# PCB-BI8-1x8.net
KiCad netlist of a schematic drawn in EAGLE
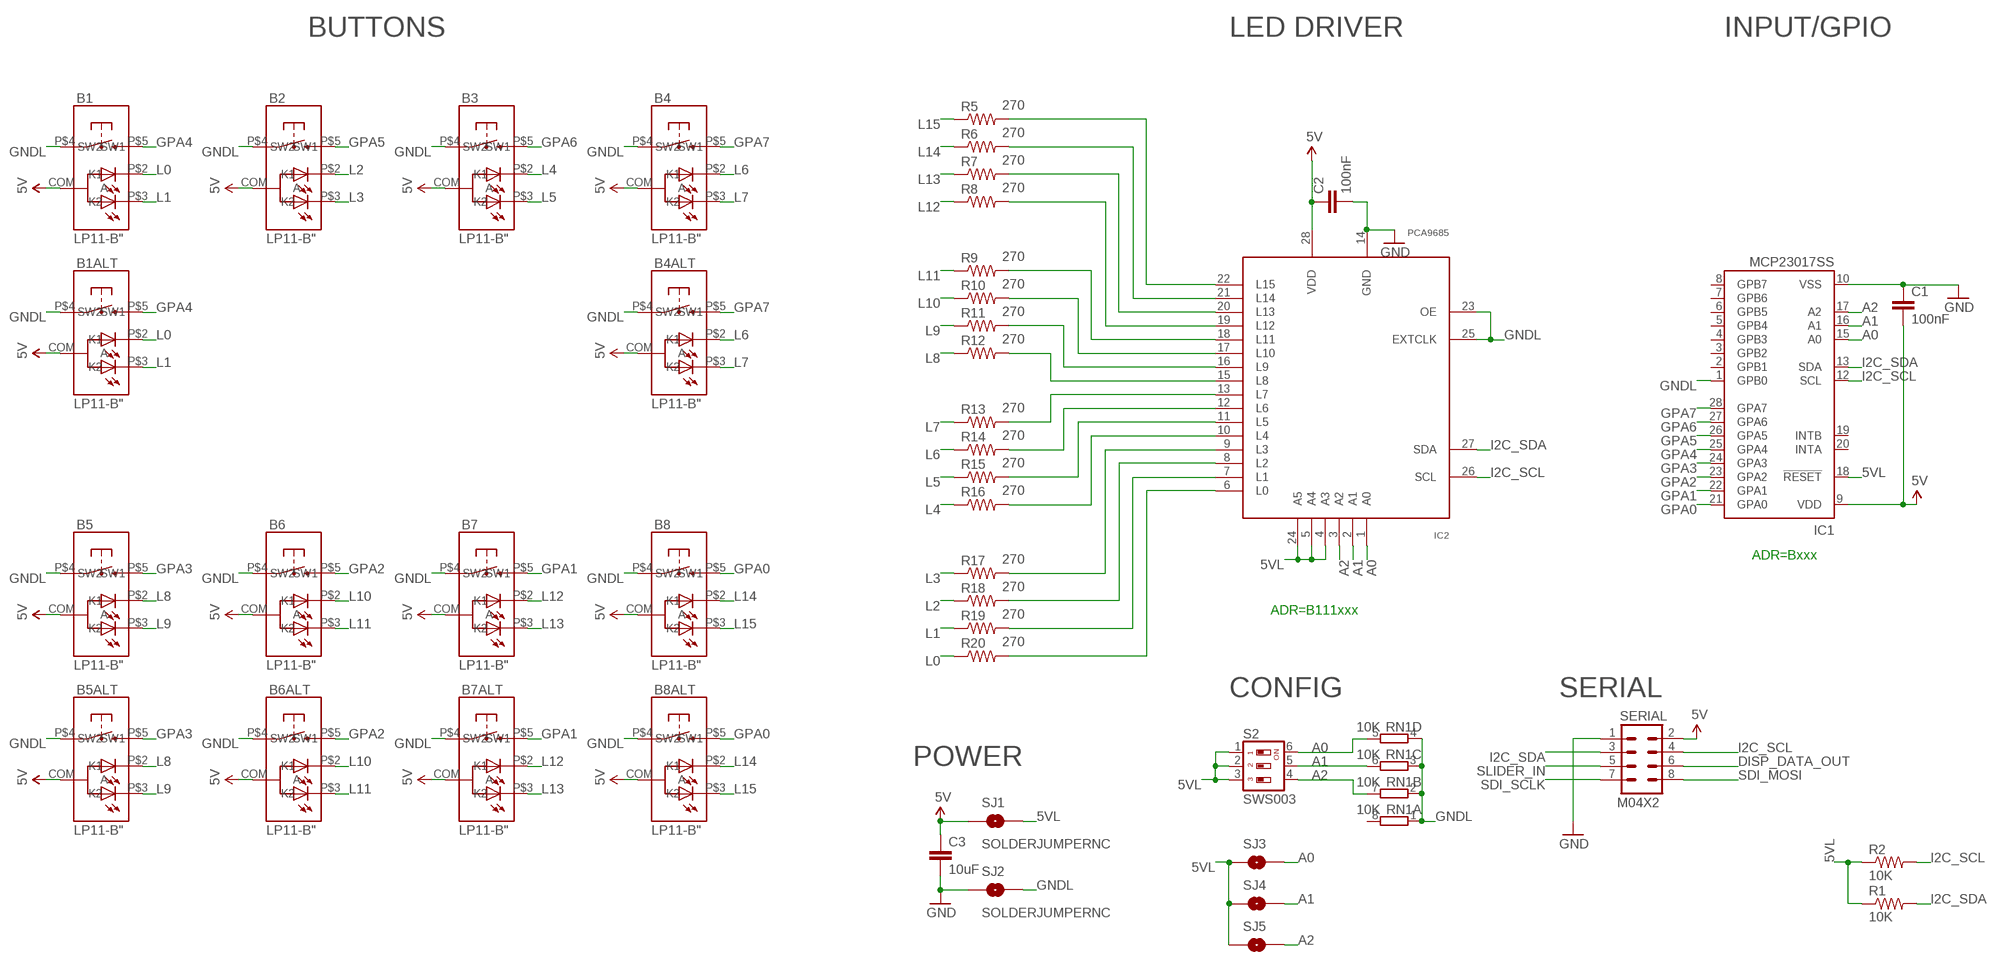
[diagram p0: schematic, sheet 1]

(export (version "E")
  (design (tool "Eeschema 10.0.6"))
  (components
    (comp (ref "B1")
      (value "LP11-B\"")
      (footprint "eagle-import:LP11")
      (libsource (lib "eagle-import") (part "LP11-B{dblquote}"))
    )
    (comp (ref "B1ALT")
      (value "LP11-B\"")
      (footprint "eagle-import:LP11")
      (libsource (lib "eagle-import") (part "LP11-B{dblquote}"))
    )
    (comp (ref "B2")
      (value "LP11-B\"")
      (footprint "eagle-import:LP11")
      (libsource (lib "eagle-import") (part "LP11-B{dblquote}"))
    )
    (comp (ref "B3")
      (value "LP11-B\"")
      (footprint "eagle-import:LP11")
      (libsource (lib "eagle-import") (part "LP11-B{dblquote}"))
    )
    (comp (ref "B4")
      (value "LP11-B\"")
      (footprint "eagle-import:LP11")
      (libsource (lib "eagle-import") (part "LP11-B{dblquote}"))
    )
    (comp (ref "B4ALT")
      (value "LP11-B\"")
      (footprint "eagle-import:LP11")
      (libsource (lib "eagle-import") (part "LP11-B{dblquote}"))
    )
    (comp (ref "B5")
      (value "LP11-B\"")
      (footprint "eagle-import:LP11")
      (libsource (lib "eagle-import") (part "LP11-B{dblquote}"))
    )
    (comp (ref "B5ALT")
      (value "LP11-B\"")
      (footprint "eagle-import:LP11")
      (libsource (lib "eagle-import") (part "LP11-B{dblquote}"))
    )
    (comp (ref "B6")
      (value "LP11-B\"")
      (footprint "eagle-import:LP11")
      (libsource (lib "eagle-import") (part "LP11-B{dblquote}"))
    )
    (comp (ref "B6ALT")
      (value "LP11-B\"")
      (footprint "eagle-import:LP11")
      (libsource (lib "eagle-import") (part "LP11-B{dblquote}"))
    )
    (comp (ref "B7")
      (value "LP11-B\"")
      (footprint "eagle-import:LP11")
      (libsource (lib "eagle-import") (part "LP11-B{dblquote}"))
    )
    (comp (ref "B7ALT")
      (value "LP11-B\"")
      (footprint "eagle-import:LP11")
      (libsource (lib "eagle-import") (part "LP11-B{dblquote}"))
    )
    (comp (ref "B8")
      (value "LP11-B\"")
      (footprint "eagle-import:LP11")
      (libsource (lib "eagle-import") (part "LP11-B{dblquote}"))
    )
    (comp (ref "B8ALT")
      (value "LP11-B\"")
      (footprint "eagle-import:LP11")
      (libsource (lib "eagle-import") (part "LP11-B{dblquote}"))
    )
    (comp (ref "C1")
      (value "100nF")
      (footprint "eagle-import:0603-CAP")
      (libsource (lib "eagle-import") (part "CAP0603-CAP"))
    )
    (comp (ref "C2")
      (value "100nF")
      (footprint "eagle-import:0603-CAP")
      (libsource (lib "eagle-import") (part "CAP0603-CAP"))
    )
    (comp (ref "C3")
      (value "10uF")
      (footprint "eagle-import:0805")
      (libsource (lib "eagle-import") (part "CAP0805"))
    )
    (comp (ref "IC1")
      (value "MCP23017SS")
      (footprint "eagle-import:SSOP28")
      (fields
        (field (name "MF") "MICROCHIP")
        (field (name "MPN") "MCP23017-E/SS")
        (field (name "MPN_1") "MCP23017-E/SS")
        (field (name "OC_FARNELL") "1467674")
        (field (name "OC_NEWARK") "31K2960")
      )
      (libsource (lib "eagle-import") (part "MCP23017SS"))
    )
    (comp (ref "IC2")
      (value "PCA9685")
      (footprint "eagle-import:TSSOP28")
      (libsource (lib "eagle-import") (part "PCA9685"))
    )
    (comp (ref "R1")
      (value "10K")
      (footprint "eagle-import:0603-RES")
      (libsource (lib "eagle-import") (part "RESISTOR0603-RES"))
    )
    (comp (ref "R2")
      (value "10K")
      (footprint "eagle-import:0603-RES")
      (libsource (lib "eagle-import") (part "RESISTOR0603-RES"))
    )
    (comp (ref "R5")
      (value "270")
      (footprint "eagle-import:0603-RES")
      (libsource (lib "eagle-import") (part "RESISTOR0603-RES"))
    )
    (comp (ref "R6")
      (value "270")
      (footprint "eagle-import:0603-RES")
      (libsource (lib "eagle-import") (part "RESISTOR0603-RES"))
    )
    (comp (ref "R7")
      (value "270")
      (footprint "eagle-import:0603-RES")
      (libsource (lib "eagle-import") (part "RESISTOR0603-RES"))
    )
    (comp (ref "R8")
      (value "270")
      (footprint "eagle-import:0603-RES")
      (libsource (lib "eagle-import") (part "RESISTOR0603-RES"))
    )
    (comp (ref "R9")
      (value "270")
      (footprint "eagle-import:0603-RES")
      (libsource (lib "eagle-import") (part "RESISTOR0603-RES"))
    )
    (comp (ref "R10")
      (value "270")
      (footprint "eagle-import:0603-RES")
      (libsource (lib "eagle-import") (part "RESISTOR0603-RES"))
    )
    (comp (ref "R11")
      (value "270")
      (footprint "eagle-import:0603-RES")
      (libsource (lib "eagle-import") (part "RESISTOR0603-RES"))
    )
    (comp (ref "R12")
      (value "270")
      (footprint "eagle-import:0603-RES")
      (libsource (lib "eagle-import") (part "RESISTOR0603-RES"))
    )
    (comp (ref "R13")
      (value "270")
      (footprint "eagle-import:0603-RES")
      (libsource (lib "eagle-import") (part "RESISTOR0603-RES"))
    )
    (comp (ref "R14")
      (value "270")
      (footprint "eagle-import:0603-RES")
      (libsource (lib "eagle-import") (part "RESISTOR0603-RES"))
    )
    (comp (ref "R15")
      (value "270")
      (footprint "eagle-import:0603-RES")
      (libsource (lib "eagle-import") (part "RESISTOR0603-RES"))
    )
    (comp (ref "R16")
      (value "270")
      (footprint "eagle-import:0603-RES")
      (libsource (lib "eagle-import") (part "RESISTOR0603-RES"))
    )
    (comp (ref "R17")
      (value "270")
      (footprint "eagle-import:0603-RES")
      (libsource (lib "eagle-import") (part "RESISTOR0603-RES"))
    )
    (comp (ref "R18")
      (value "270")
      (footprint "eagle-import:0603-RES")
      (libsource (lib "eagle-import") (part "RESISTOR0603-RES"))
    )
    (comp (ref "R19")
      (value "270")
      (footprint "eagle-import:0603-RES")
      (libsource (lib "eagle-import") (part "RESISTOR0603-RES"))
    )
    (comp (ref "R20")
      (value "270")
      (footprint "eagle-import:0603-RES")
      (libsource (lib "eagle-import") (part "RESISTOR0603-RES"))
    )
    (comp (ref "RN1")
      (value "10K")
      (footprint "eagle-import:CAY16_HAND")
      (libsource (lib "eagle-import") (part "4R-NCAY16"))
    )
    (comp (ref "S2")
      (value "SWS003")
      (footprint "eagle-import:SMS-003")
      (libsource (lib "eagle-import") (part "SWS003"))
    )
    (comp (ref "SERIAL")
      (value "M04X2")
      (footprint "eagle-import:2X4")
      (libsource (lib "eagle-import") (part "M04X2"))
    )
    (comp (ref "SJ1")
      (value "SOLDERJUMPERNC")
      (footprint "eagle-import:SJ_2S")
      (libsource (lib "eagle-import") (part "SOLDERJUMPERNC"))
    )
    (comp (ref "SJ2")
      (value "SOLDERJUMPERNC")
      (footprint "eagle-import:SJ_2S")
      (libsource (lib "eagle-import") (part "SOLDERJUMPERNC"))
    )
    (comp (ref "SJ3")
      (value "SOLDERJUMPERNC")
      (footprint "eagle-import:SJ_2S")
      (libsource (lib "eagle-import") (part "SOLDERJUMPERNC"))
    )
    (comp (ref "SJ4")
      (value "SOLDERJUMPERNC")
      (footprint "eagle-import:SJ_2S")
      (libsource (lib "eagle-import") (part "SOLDERJUMPERNC"))
    )
    (comp (ref "SJ5")
      (value "SOLDERJUMPERNC")
      (footprint "eagle-import:SJ_2S")
      (libsource (lib "eagle-import") (part "SOLDERJUMPERNC"))
    )
  )
  (nets
    (net (code "1") (name "/5VL") (class "Default")
      (node (ref "IC1") (pin "18") (pinfunction "~{RESET}_18") (pintype "input"))
      (node (ref "IC2") (pin "24") (pinfunction "A5_24") (pintype "input"))
      (node (ref "IC2") (pin "4") (pinfunction "A3_4") (pintype "input"))
      (node (ref "IC2") (pin "5") (pinfunction "A4_5") (pintype "input"))
      (node (ref "R1") (pin "1") (pinfunction "1_1") (pintype "passive"))
      (node (ref "R2") (pin "1") (pinfunction "1_1") (pintype "passive"))
      (node (ref "S2") (pin "1") (pinfunction "1_1") (pintype "passive"))
      (node (ref "S2") (pin "2") (pinfunction "2_2") (pintype "passive"))
      (node (ref "S2") (pin "3") (pinfunction "3_3") (pintype "passive"))
      (node (ref "SJ1") (pin "2") (pinfunction "2_2") (pintype "passive"))
      (node (ref "SJ3") (pin "1") (pinfunction "1_1") (pintype "passive"))
      (node (ref "SJ4") (pin "1") (pinfunction "1_1") (pintype "passive"))
      (node (ref "SJ5") (pin "1") (pinfunction "1_1") (pintype "passive"))
    )
    (net (code "2") (name "/A0") (class "Default")
      (node (ref "IC1") (pin "15") (pinfunction "A0_15") (pintype "input"))
      (node (ref "IC2") (pin "1") (pinfunction "A0_1") (pintype "input"))
      (node (ref "RN1") (pin "5") (pinfunction "2_5") (pintype "passive"))
      (node (ref "S2") (pin "6") (pinfunction "6_6") (pintype "passive"))
      (node (ref "SJ3") (pin "2") (pinfunction "2_2") (pintype "passive"))
    )
    (net (code "3") (name "/A1") (class "Default")
      (node (ref "IC1") (pin "16") (pinfunction "A1_16") (pintype "input"))
      (node (ref "IC2") (pin "2") (pinfunction "A1_2") (pintype "input"))
      (node (ref "RN1") (pin "6") (pinfunction "2_6") (pintype "passive"))
      (node (ref "S2") (pin "5") (pinfunction "5_5") (pintype "passive"))
      (node (ref "SJ4") (pin "2") (pinfunction "2_2") (pintype "passive"))
    )
    (net (code "4") (name "/A2") (class "Default")
      (node (ref "IC1") (pin "17") (pinfunction "A2_17") (pintype "input"))
      (node (ref "IC2") (pin "3") (pinfunction "A2_3") (pintype "input"))
      (node (ref "RN1") (pin "7") (pinfunction "2_7") (pintype "passive"))
      (node (ref "S2") (pin "4") (pinfunction "4_4") (pintype "passive"))
      (node (ref "SJ5") (pin "2") (pinfunction "2_2") (pintype "passive"))
    )
    (net (code "5") (name "/DISP_DATA_OUT") (class "Default")
      (node (ref "SERIAL") (pin "6") (pinfunction "6_6") (pintype "passive"))
    )
    (net (code "6") (name "/GNDL") (class "Default")
      (node (ref "B1") (pin "P$4") (pinfunction "SW1_P$4") (pintype "bidirectional"))
      (node (ref "B1ALT") (pin "P$4") (pinfunction "SW1_P$4") (pintype "bidirectional"))
      (node (ref "B2") (pin "P$4") (pinfunction "SW1_P$4") (pintype "bidirectional"))
      (node (ref "B3") (pin "P$4") (pinfunction "SW1_P$4") (pintype "bidirectional"))
      (node (ref "B4") (pin "P$4") (pinfunction "SW1_P$4") (pintype "bidirectional"))
      (node (ref "B4ALT") (pin "P$4") (pinfunction "SW1_P$4") (pintype "bidirectional"))
      (node (ref "B5") (pin "P$4") (pinfunction "SW1_P$4") (pintype "bidirectional"))
      (node (ref "B5ALT") (pin "P$4") (pinfunction "SW1_P$4") (pintype "bidirectional"))
      (node (ref "B6") (pin "P$4") (pinfunction "SW1_P$4") (pintype "bidirectional"))
      (node (ref "B6ALT") (pin "P$4") (pinfunction "SW1_P$4") (pintype "bidirectional"))
      (node (ref "B7") (pin "P$4") (pinfunction "SW1_P$4") (pintype "bidirectional"))
      (node (ref "B7ALT") (pin "P$4") (pinfunction "SW1_P$4") (pintype "bidirectional"))
      (node (ref "B8") (pin "P$4") (pinfunction "SW1_P$4") (pintype "bidirectional"))
      (node (ref "B8ALT") (pin "P$4") (pinfunction "SW1_P$4") (pintype "bidirectional"))
      (node (ref "IC1") (pin "1") (pinfunction "GPB0_1") (pintype "bidirectional"))
      (node (ref "IC2") (pin "23") (pinfunction "OE_23") (pintype "input"))
      (node (ref "IC2") (pin "25") (pinfunction "EXTCLK_25") (pintype "input"))
      (node (ref "RN1") (pin "1") (pinfunction "1_1") (pintype "passive"))
      (node (ref "RN1") (pin "2") (pinfunction "1_2") (pintype "passive"))
      (node (ref "RN1") (pin "3") (pinfunction "1_3") (pintype "passive"))
      (node (ref "RN1") (pin "4") (pinfunction "1_4") (pintype "passive"))
      (node (ref "SJ2") (pin "2") (pinfunction "2_2") (pintype "passive"))
    )
    (net (code "7") (name "/GPA0") (class "Default")
      (node (ref "B8") (pin "P$5") (pinfunction "SW2_P$5") (pintype "bidirectional"))
      (node (ref "B8ALT") (pin "P$5") (pinfunction "SW2_P$5") (pintype "bidirectional"))
      (node (ref "IC1") (pin "21") (pinfunction "GPA0_21") (pintype "bidirectional"))
    )
    (net (code "8") (name "/GPA1") (class "Default")
      (node (ref "B7") (pin "P$5") (pinfunction "SW2_P$5") (pintype "bidirectional"))
      (node (ref "B7ALT") (pin "P$5") (pinfunction "SW2_P$5") (pintype "bidirectional"))
      (node (ref "IC1") (pin "22") (pinfunction "GPA1_22") (pintype "bidirectional"))
    )
    (net (code "9") (name "/GPA2") (class "Default")
      (node (ref "B6") (pin "P$5") (pinfunction "SW2_P$5") (pintype "bidirectional"))
      (node (ref "B6ALT") (pin "P$5") (pinfunction "SW2_P$5") (pintype "bidirectional"))
      (node (ref "IC1") (pin "23") (pinfunction "GPA2_23") (pintype "bidirectional"))
    )
    (net (code "10") (name "/GPA3") (class "Default")
      (node (ref "B5") (pin "P$5") (pinfunction "SW2_P$5") (pintype "bidirectional"))
      (node (ref "B5ALT") (pin "P$5") (pinfunction "SW2_P$5") (pintype "bidirectional"))
      (node (ref "IC1") (pin "24") (pinfunction "GPA3_24") (pintype "bidirectional"))
    )
    (net (code "11") (name "/GPA4") (class "Default")
      (node (ref "B1") (pin "P$5") (pinfunction "SW2_P$5") (pintype "bidirectional"))
      (node (ref "B1ALT") (pin "P$5") (pinfunction "SW2_P$5") (pintype "bidirectional"))
      (node (ref "IC1") (pin "25") (pinfunction "GPA4_25") (pintype "bidirectional"))
    )
    (net (code "12") (name "/GPA5") (class "Default")
      (node (ref "B2") (pin "P$5") (pinfunction "SW2_P$5") (pintype "bidirectional"))
      (node (ref "IC1") (pin "26") (pinfunction "GPA5_26") (pintype "bidirectional"))
    )
    (net (code "13") (name "/GPA6") (class "Default")
      (node (ref "B3") (pin "P$5") (pinfunction "SW2_P$5") (pintype "bidirectional"))
      (node (ref "IC1") (pin "27") (pinfunction "GPA6_27") (pintype "bidirectional"))
    )
    (net (code "14") (name "/GPA7") (class "Default")
      (node (ref "B4") (pin "P$5") (pinfunction "SW2_P$5") (pintype "bidirectional"))
      (node (ref "B4ALT") (pin "P$5") (pinfunction "SW2_P$5") (pintype "bidirectional"))
      (node (ref "IC1") (pin "28") (pinfunction "GPA7_28") (pintype "bidirectional"))
    )
    (net (code "15") (name "/I2C_SCL") (class "Default")
      (node (ref "IC1") (pin "12") (pinfunction "SCL_12") (pintype "input"))
      (node (ref "IC2") (pin "26") (pinfunction "SCL_26") (pintype "input"))
      (node (ref "R2") (pin "2") (pinfunction "2_2") (pintype "passive"))
      (node (ref "SERIAL") (pin "4") (pinfunction "4_4") (pintype "passive"))
    )
    (net (code "16") (name "/I2C_SDA") (class "Default")
      (node (ref "IC1") (pin "13") (pinfunction "SDA_13") (pintype "bidirectional"))
      (node (ref "IC2") (pin "27") (pinfunction "SDA_27") (pintype "input"))
      (node (ref "R1") (pin "2") (pinfunction "2_2") (pintype "passive"))
      (node (ref "SERIAL") (pin "3") (pinfunction "3_3") (pintype "passive"))
    )
    (net (code "17") (name "/L0") (class "Default")
      (node (ref "B1") (pin "P$2") (pinfunction "K1_P$2") (pintype "bidirectional"))
      (node (ref "B1ALT") (pin "P$2") (pinfunction "K1_P$2") (pintype "bidirectional"))
      (node (ref "R20") (pin "1") (pinfunction "1_1") (pintype "passive"))
    )
    (net (code "18") (name "/L1") (class "Default")
      (node (ref "B1") (pin "P$3") (pinfunction "K2_P$3") (pintype "bidirectional"))
      (node (ref "B1ALT") (pin "P$3") (pinfunction "K2_P$3") (pintype "bidirectional"))
      (node (ref "R19") (pin "1") (pinfunction "1_1") (pintype "passive"))
    )
    (net (code "19") (name "/L2") (class "Default")
      (node (ref "B2") (pin "P$2") (pinfunction "K1_P$2") (pintype "bidirectional"))
      (node (ref "R18") (pin "1") (pinfunction "1_1") (pintype "passive"))
    )
    (net (code "20") (name "/L3") (class "Default")
      (node (ref "B2") (pin "P$3") (pinfunction "K2_P$3") (pintype "bidirectional"))
      (node (ref "R17") (pin "1") (pinfunction "1_1") (pintype "passive"))
    )
    (net (code "21") (name "/L4") (class "Default")
      (node (ref "B3") (pin "P$2") (pinfunction "K1_P$2") (pintype "bidirectional"))
      (node (ref "R16") (pin "1") (pinfunction "1_1") (pintype "passive"))
    )
    (net (code "22") (name "/L5") (class "Default")
      (node (ref "B3") (pin "P$3") (pinfunction "K2_P$3") (pintype "bidirectional"))
      (node (ref "R15") (pin "1") (pinfunction "1_1") (pintype "passive"))
    )
    (net (code "23") (name "/L6") (class "Default")
      (node (ref "B4") (pin "P$2") (pinfunction "K1_P$2") (pintype "bidirectional"))
      (node (ref "B4ALT") (pin "P$2") (pinfunction "K1_P$2") (pintype "bidirectional"))
      (node (ref "R14") (pin "1") (pinfunction "1_1") (pintype "passive"))
    )
    (net (code "24") (name "/L7") (class "Default")
      (node (ref "B4") (pin "P$3") (pinfunction "K2_P$3") (pintype "bidirectional"))
      (node (ref "B4ALT") (pin "P$3") (pinfunction "K2_P$3") (pintype "bidirectional"))
      (node (ref "R13") (pin "1") (pinfunction "1_1") (pintype "passive"))
    )
    (net (code "25") (name "/L8") (class "Default")
      (node (ref "B5") (pin "P$2") (pinfunction "K1_P$2") (pintype "bidirectional"))
      (node (ref "B5ALT") (pin "P$2") (pinfunction "K1_P$2") (pintype "bidirectional"))
      (node (ref "R12") (pin "1") (pinfunction "1_1") (pintype "passive"))
    )
    (net (code "26") (name "/L9") (class "Default")
      (node (ref "B5") (pin "P$3") (pinfunction "K2_P$3") (pintype "bidirectional"))
      (node (ref "B5ALT") (pin "P$3") (pinfunction "K2_P$3") (pintype "bidirectional"))
      (node (ref "R11") (pin "1") (pinfunction "1_1") (pintype "passive"))
    )
    (net (code "27") (name "/L10") (class "Default")
      (node (ref "B6") (pin "P$2") (pinfunction "K1_P$2") (pintype "bidirectional"))
      (node (ref "B6ALT") (pin "P$2") (pinfunction "K1_P$2") (pintype "bidirectional"))
      (node (ref "R10") (pin "1") (pinfunction "1_1") (pintype "passive"))
    )
    (net (code "28") (name "/L11") (class "Default")
      (node (ref "B6") (pin "P$3") (pinfunction "K2_P$3") (pintype "bidirectional"))
      (node (ref "B6ALT") (pin "P$3") (pinfunction "K2_P$3") (pintype "bidirectional"))
      (node (ref "R9") (pin "1") (pinfunction "1_1") (pintype "passive"))
    )
    (net (code "29") (name "/L12") (class "Default")
      (node (ref "B7") (pin "P$2") (pinfunction "K1_P$2") (pintype "bidirectional"))
      (node (ref "B7ALT") (pin "P$2") (pinfunction "K1_P$2") (pintype "bidirectional"))
      (node (ref "R8") (pin "1") (pinfunction "1_1") (pintype "passive"))
    )
    (net (code "30") (name "/L13") (class "Default")
      (node (ref "B7") (pin "P$3") (pinfunction "K2_P$3") (pintype "bidirectional"))
      (node (ref "B7ALT") (pin "P$3") (pinfunction "K2_P$3") (pintype "bidirectional"))
      (node (ref "R7") (pin "1") (pinfunction "1_1") (pintype "passive"))
    )
    (net (code "31") (name "/L14") (class "Default")
      (node (ref "B8") (pin "P$2") (pinfunction "K1_P$2") (pintype "bidirectional"))
      (node (ref "B8ALT") (pin "P$2") (pinfunction "K1_P$2") (pintype "bidirectional"))
      (node (ref "R6") (pin "1") (pinfunction "1_1") (pintype "passive"))
    )
    (net (code "32") (name "/L15") (class "Default")
      (node (ref "B8") (pin "P$3") (pinfunction "K2_P$3") (pintype "bidirectional"))
      (node (ref "B8ALT") (pin "P$3") (pinfunction "K2_P$3") (pintype "bidirectional"))
      (node (ref "R5") (pin "1") (pinfunction "1_1") (pintype "passive"))
    )
    (net (code "33") (name "/SDI_MOSI") (class "Default")
      (node (ref "SERIAL") (pin "8") (pinfunction "8_8") (pintype "passive"))
    )
    (net (code "34") (name "/SDI_SCLK") (class "Default")
      (node (ref "SERIAL") (pin "7") (pinfunction "7_7") (pintype "passive"))
    )
    (net (code "35") (name "/SLIDER_IN") (class "Default")
      (node (ref "SERIAL") (pin "5") (pinfunction "5_5") (pintype "passive"))
    )
    (net (code "36") (name "5V") (class "Default")
      (node (ref "B1") (pin "COM") (pinfunction "A_COM") (pintype "bidirectional"))
      (node (ref "B1ALT") (pin "COM") (pinfunction "A_COM") (pintype "bidirectional"))
      (node (ref "B2") (pin "COM") (pinfunction "A_COM") (pintype "bidirectional"))
      (node (ref "B3") (pin "COM") (pinfunction "A_COM") (pintype "bidirectional"))
      (node (ref "B4") (pin "COM") (pinfunction "A_COM") (pintype "bidirectional"))
      (node (ref "B4ALT") (pin "COM") (pinfunction "A_COM") (pintype "bidirectional"))
      (node (ref "B5") (pin "COM") (pinfunction "A_COM") (pintype "bidirectional"))
      (node (ref "B5ALT") (pin "COM") (pinfunction "A_COM") (pintype "bidirectional"))
      (node (ref "B6") (pin "COM") (pinfunction "A_COM") (pintype "bidirectional"))
      (node (ref "B6ALT") (pin "COM") (pinfunction "A_COM") (pintype "bidirectional"))
      (node (ref "B7") (pin "COM") (pinfunction "A_COM") (pintype "bidirectional"))
      (node (ref "B7ALT") (pin "COM") (pinfunction "A_COM") (pintype "bidirectional"))
      (node (ref "B8") (pin "COM") (pinfunction "A_COM") (pintype "bidirectional"))
      (node (ref "B8ALT") (pin "COM") (pinfunction "A_COM") (pintype "bidirectional"))
      (node (ref "C1") (pin "2") (pinfunction "2_2") (pintype "passive"))
      (node (ref "C2") (pin "1") (pinfunction "1_1") (pintype "passive"))
      (node (ref "C3") (pin "1") (pinfunction "1_1") (pintype "passive"))
      (node (ref "IC1") (pin "9") (pinfunction "VDD_9") (pintype "power_in"))
      (node (ref "IC2") (pin "28") (pinfunction "VDD_28") (pintype "power_in"))
      (node (ref "SERIAL") (pin "2") (pinfunction "2_2") (pintype "passive"))
      (node (ref "SJ1") (pin "1") (pinfunction "1_1") (pintype "passive"))
    )
    (net (code "37") (name "GND") (class "Default")
      (node (ref "C1") (pin "1") (pinfunction "1_1") (pintype "passive"))
      (node (ref "C2") (pin "2") (pinfunction "2_2") (pintype "passive"))
      (node (ref "C3") (pin "2") (pinfunction "2_2") (pintype "passive"))
      (node (ref "IC1") (pin "10") (pinfunction "VSS_10") (pintype "power_in"))
      (node (ref "IC2") (pin "14") (pinfunction "GND_14") (pintype "power_in"))
      (node (ref "SERIAL") (pin "1") (pinfunction "1_1") (pintype "passive"))
      (node (ref "SJ2") (pin "1") (pinfunction "1_1") (pintype "passive"))
    )
    (net (code "38") (name "Net-(IC2-L0)") (class "Default")
      (node (ref "IC2") (pin "6") (pinfunction "L0_6") (pintype "output"))
      (node (ref "R20") (pin "2") (pinfunction "2_2") (pintype "passive"))
    )
    (net (code "39") (name "Net-(IC2-L1)") (class "Default")
      (node (ref "IC2") (pin "7") (pinfunction "L1_7") (pintype "output"))
      (node (ref "R19") (pin "2") (pinfunction "2_2") (pintype "passive"))
    )
    (net (code "40") (name "Net-(IC2-L2)") (class "Default")
      (node (ref "IC2") (pin "8") (pinfunction "L2_8") (pintype "output"))
      (node (ref "R18") (pin "2") (pinfunction "2_2") (pintype "passive"))
    )
    (net (code "41") (name "Net-(IC2-L3)") (class "Default")
      (node (ref "IC2") (pin "9") (pinfunction "L3_9") (pintype "output"))
      (node (ref "R17") (pin "2") (pinfunction "2_2") (pintype "passive"))
    )
    (net (code "42") (name "Net-(IC2-L4)") (class "Default")
      (node (ref "IC2") (pin "10") (pinfunction "L4_10") (pintype "output"))
      (node (ref "R16") (pin "2") (pinfunction "2_2") (pintype "passive"))
    )
    (net (code "43") (name "Net-(IC2-L5)") (class "Default")
      (node (ref "IC2") (pin "11") (pinfunction "L5_11") (pintype "output"))
      (node (ref "R15") (pin "2") (pinfunction "2_2") (pintype "passive"))
    )
    (net (code "44") (name "Net-(IC2-L6)") (class "Default")
      (node (ref "IC2") (pin "12") (pinfunction "L6_12") (pintype "output"))
      (node (ref "R14") (pin "2") (pinfunction "2_2") (pintype "passive"))
    )
    (net (code "45") (name "Net-(IC2-L7)") (class "Default")
      (node (ref "IC2") (pin "13") (pinfunction "L7_13") (pintype "output"))
      (node (ref "R13") (pin "2") (pinfunction "2_2") (pintype "passive"))
    )
    (net (code "46") (name "Net-(IC2-L8)") (class "Default")
      (node (ref "IC2") (pin "15") (pinfunction "L8_15") (pintype "output"))
      (node (ref "R12") (pin "2") (pinfunction "2_2") (pintype "passive"))
    )
    (net (code "47") (name "Net-(IC2-L9)") (class "Default")
      (node (ref "IC2") (pin "16") (pinfunction "L9_16") (pintype "output"))
      (node (ref "R11") (pin "2") (pinfunction "2_2") (pintype "passive"))
    )
    (net (code "48") (name "Net-(IC2-L10)") (class "Default")
      (node (ref "IC2") (pin "17") (pinfunction "L10_17") (pintype "output"))
      (node (ref "R10") (pin "2") (pinfunction "2_2") (pintype "passive"))
    )
    (net (code "49") (name "Net-(IC2-L11)") (class "Default")
      (node (ref "IC2") (pin "18") (pinfunction "L11_18") (pintype "output"))
      (node (ref "R9") (pin "2") (pinfunction "2_2") (pintype "passive"))
    )
    (net (code "50") (name "Net-(IC2-L12)") (class "Default")
      (node (ref "IC2") (pin "19") (pinfunction "L12_19") (pintype "output"))
      (node (ref "R8") (pin "2") (pinfunction "2_2") (pintype "passive"))
    )
    (net (code "51") (name "Net-(IC2-L13)") (class "Default")
      (node (ref "IC2") (pin "20") (pinfunction "L13_20") (pintype "output"))
      (node (ref "R7") (pin "2") (pinfunction "2_2") (pintype "passive"))
    )
    (net (code "52") (name "Net-(IC2-L14)") (class "Default")
      (node (ref "IC2") (pin "21") (pinfunction "L14_21") (pintype "output"))
      (node (ref "R6") (pin "2") (pinfunction "2_2") (pintype "passive"))
    )
    (net (code "53") (name "Net-(IC2-L15)") (class "Default")
      (node (ref "IC2") (pin "22") (pinfunction "L15_22") (pintype "output"))
      (node (ref "R5") (pin "2") (pinfunction "2_2") (pintype "passive"))
    )
    (net (code "54") (name "unconnected-(IC1-GPB1-Pad2)") (class "Default")
      (node (ref "IC1") (pin "2") (pinfunction "GPB1_2") (pintype "bidirectional"))
    )
    (net (code "55") (name "unconnected-(IC1-GPB2-Pad3)") (class "Default")
      (node (ref "IC1") (pin "3") (pinfunction "GPB2_3") (pintype "bidirectional"))
    )
    (net (code "56") (name "unconnected-(IC1-GPB3-Pad4)") (class "Default")
      (node (ref "IC1") (pin "4") (pinfunction "GPB3_4") (pintype "bidirectional"))
    )
    (net (code "57") (name "unconnected-(IC1-GPB4-Pad5)") (class "Default")
      (node (ref "IC1") (pin "5") (pinfunction "GPB4_5") (pintype "bidirectional"))
    )
    (net (code "58") (name "unconnected-(IC1-GPB5-Pad6)") (class "Default")
      (node (ref "IC1") (pin "6") (pinfunction "GPB5_6") (pintype "bidirectional"))
    )
    (net (code "59") (name "unconnected-(IC1-GPB6-Pad7)") (class "Default")
      (node (ref "IC1") (pin "7") (pinfunction "GPB6_7") (pintype "bidirectional"))
    )
    (net (code "60") (name "unconnected-(IC1-GPB7-Pad8)") (class "Default")
      (node (ref "IC1") (pin "8") (pinfunction "GPB7_8") (pintype "bidirectional"))
    )
    (net (code "61") (name "unconnected-(IC1-INTA-Pad20)") (class "Default")
      (node (ref "IC1") (pin "20") (pinfunction "INTA_20") (pintype "output"))
    )
    (net (code "62") (name "unconnected-(IC1-INTB-Pad19)") (class "Default")
      (node (ref "IC1") (pin "19") (pinfunction "INTB_19") (pintype "output"))
    )
    (net (code "63") (name "unconnected-(RN1A-2-Pad8)") (class "Default")
      (node (ref "RN1") (pin "8") (pinfunction "2_8") (pintype "passive"))
    )
  )
)
